# roomautomationfinal.net
KiCad netlist of a schematic drawn in EAGLE
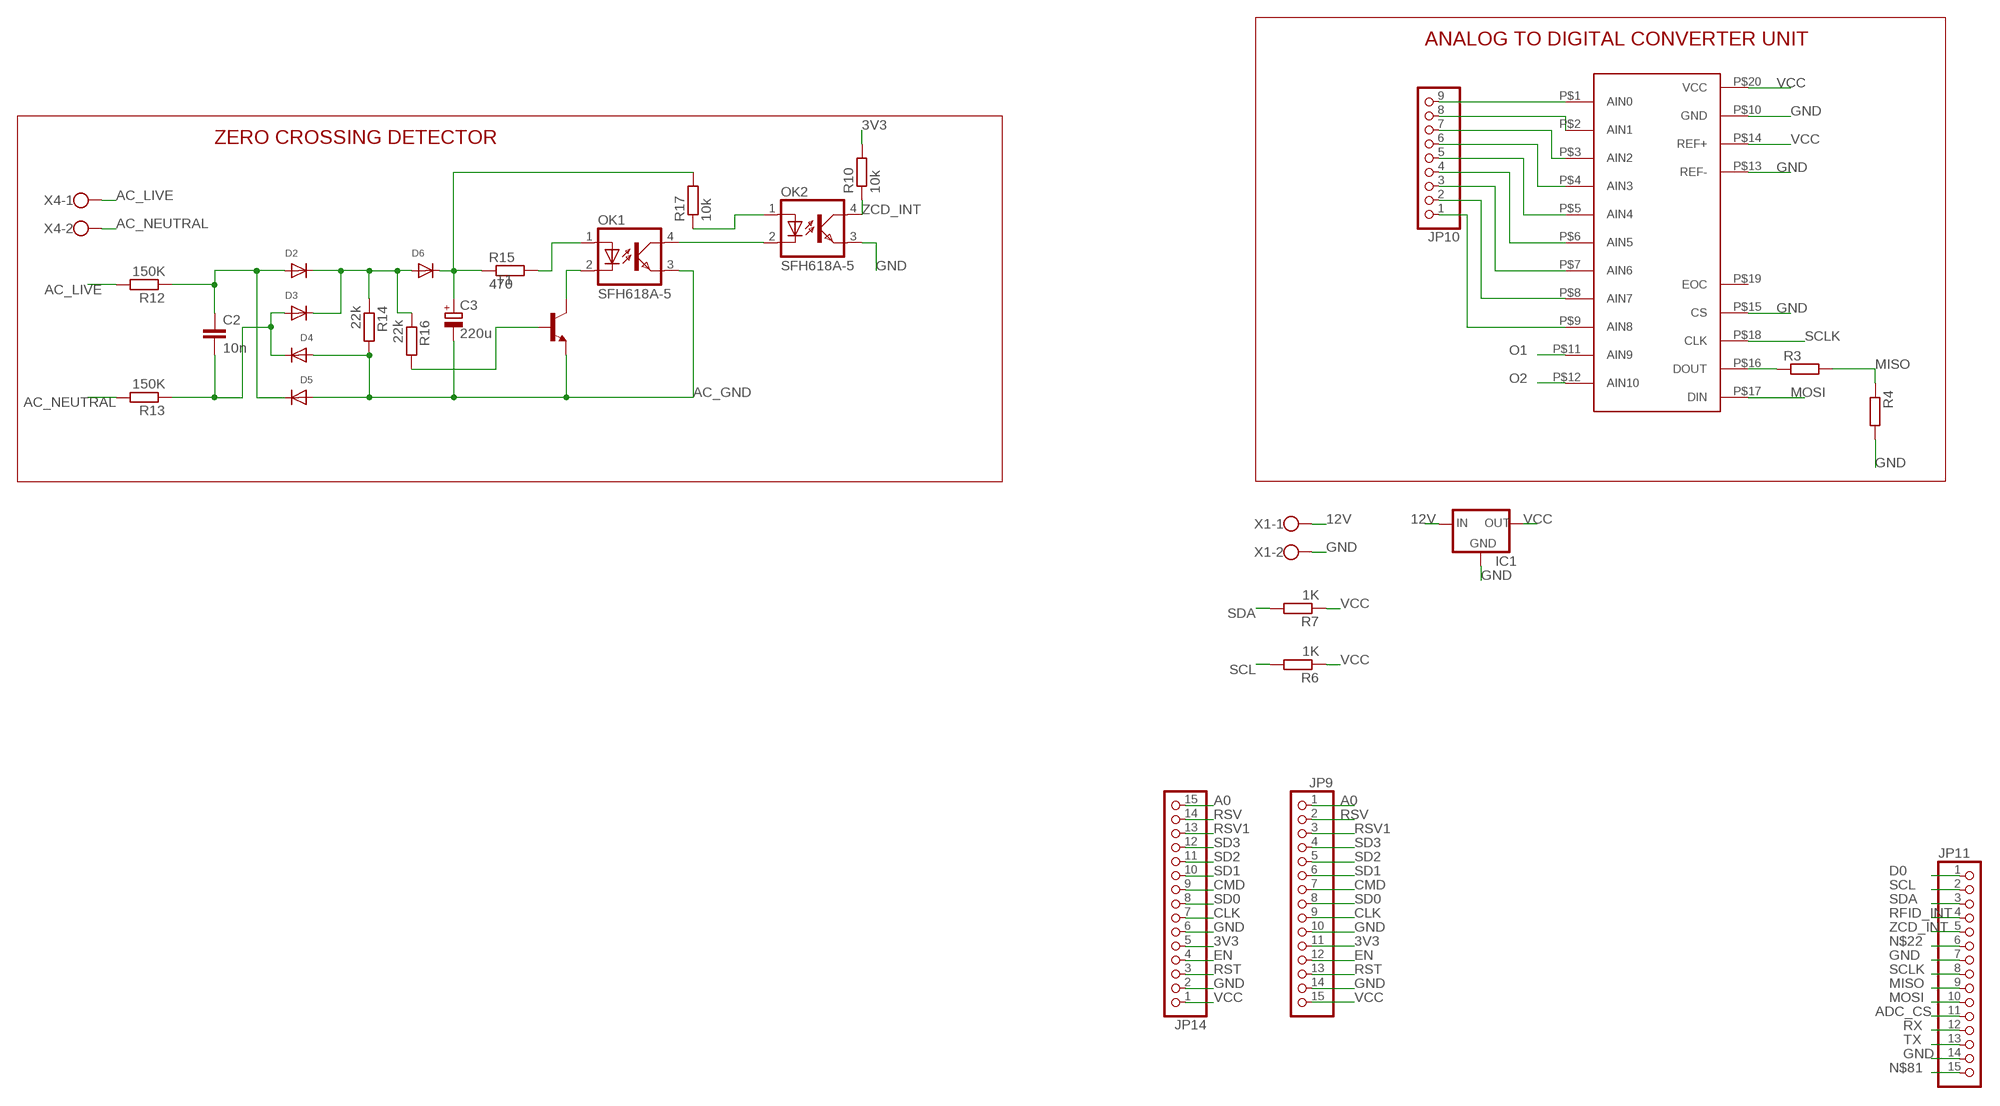
[diagram p0: schematic, sheet 1, part 1 of 2]
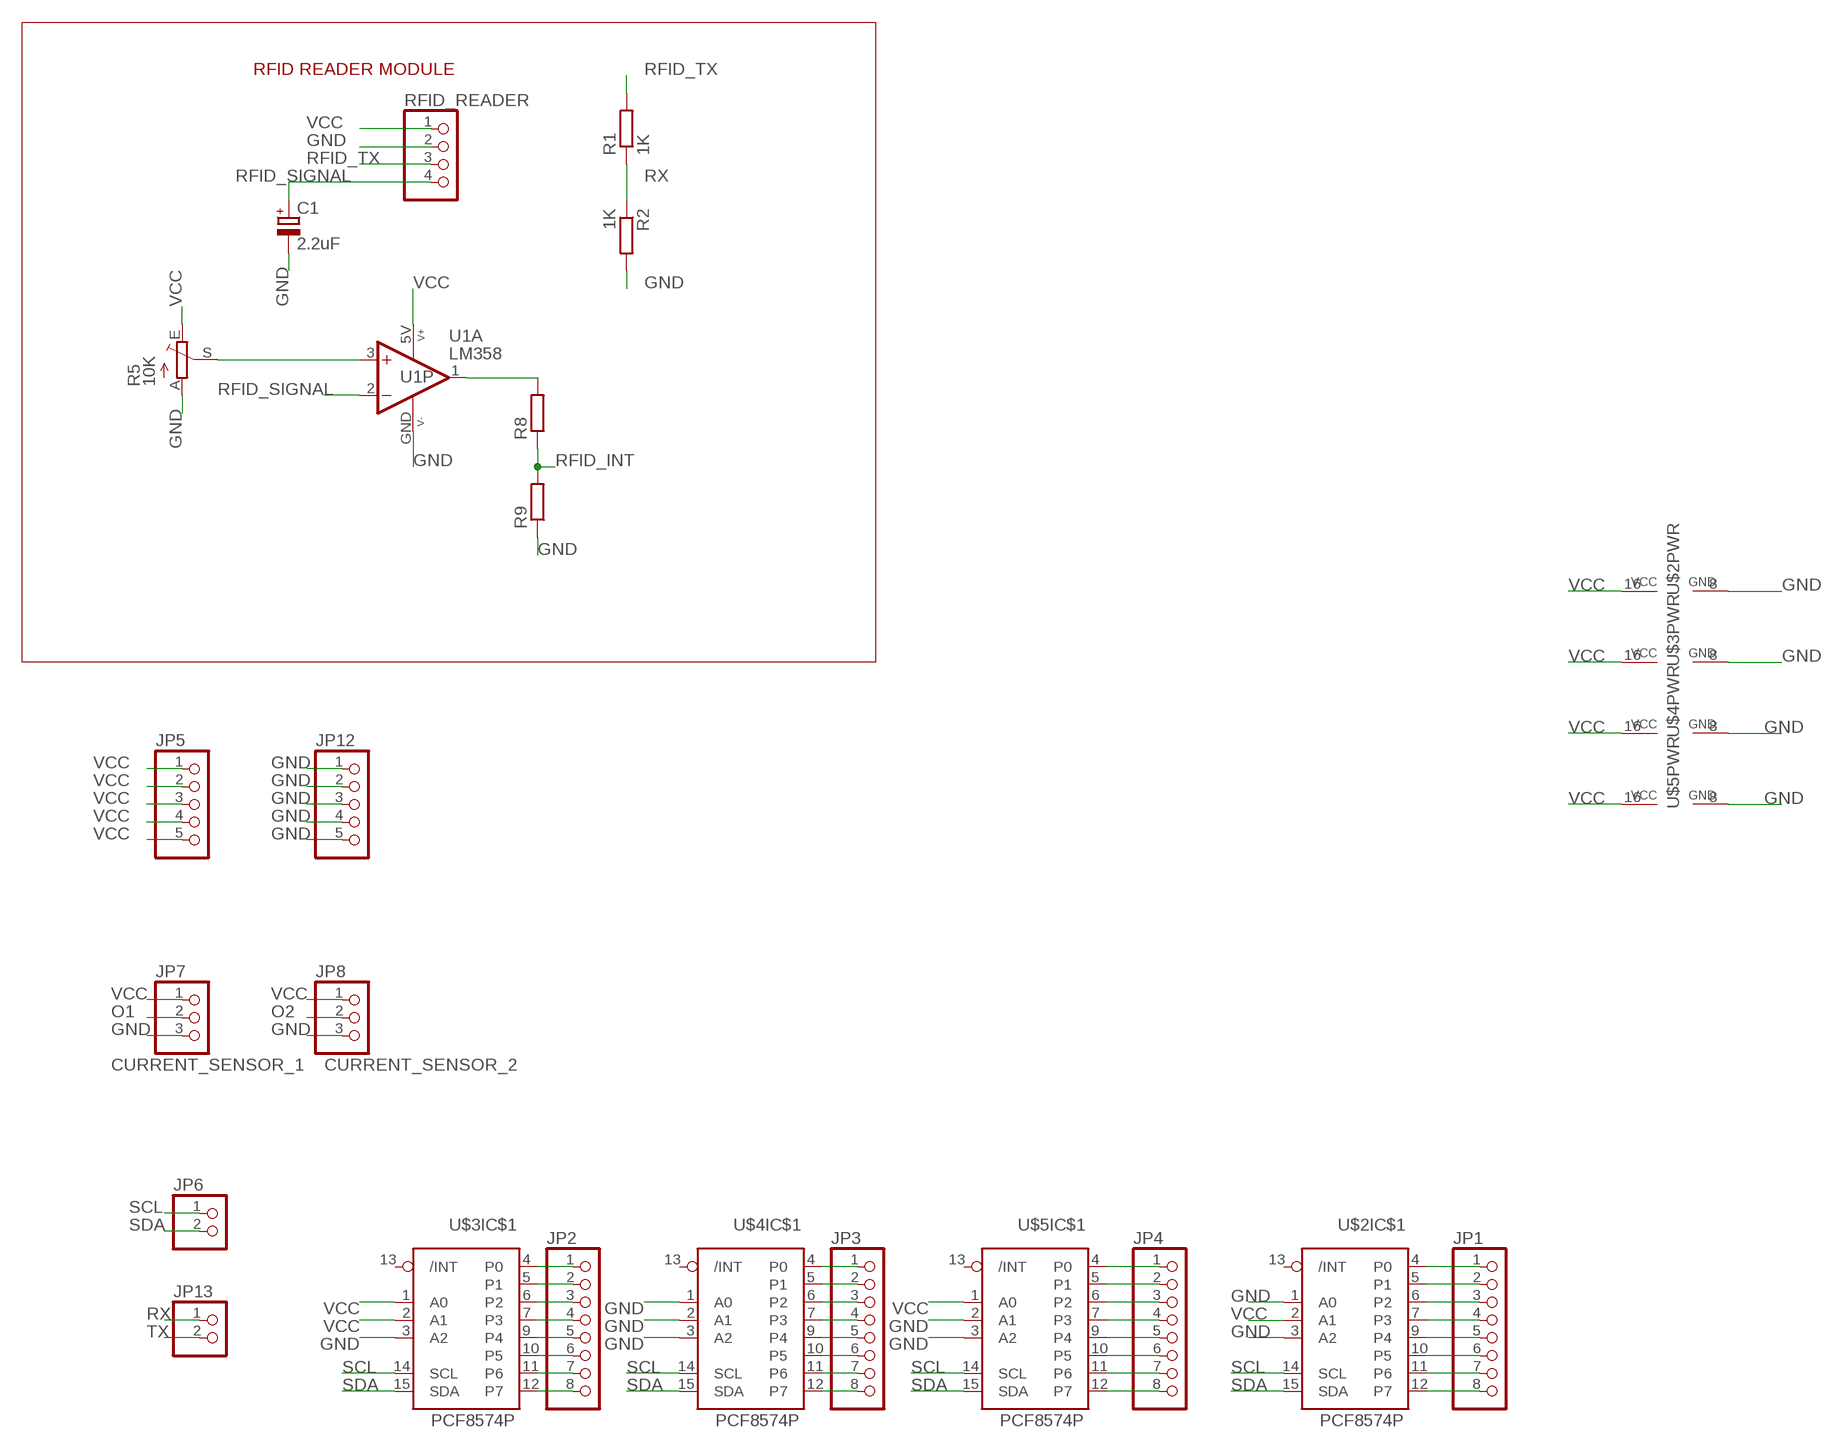
[diagram p1: schematic, sheet 1, part 2 of 2]

(export (version "E")
  (design (tool "Eeschema 10.0.6"))
  (components
    (comp (ref "C1")
      (value "2.2uF")
      (footprint "eagle-import:E2,5-5")
      (libsource (lib "eagle-import") (part "resistor_CPOL-EUE2.5-5"))
    )
    (comp (ref "C2")
      (value "10n")
      (footprint "eagle-import:C150-054X183")
      (libsource (lib "eagle-import") (part "C-EU150-054X183"))
    )
    (comp (ref "C3")
      (value "220u")
      (footprint "eagle-import:E5-10,5")
      (libsource (lib "eagle-import") (part "CPOL-EUE5-10.5"))
    )
    (comp (ref "D2")
      (value "DIODEDO-1N4148")
      (footprint "eagle-import:DO-1N4148")
      (libsource (lib "eagle-import") (part "DIODEDO-1N4148"))
    )
    (comp (ref "D3")
      (value "DIODEDO-1N4148")
      (footprint "eagle-import:DO-1N4148")
      (libsource (lib "eagle-import") (part "DIODEDO-1N4148"))
    )
    (comp (ref "D4")
      (value "DIODEDO-1N4148")
      (footprint "eagle-import:DO-1N4148")
      (libsource (lib "eagle-import") (part "DIODEDO-1N4148"))
    )
    (comp (ref "D5")
      (value "DIODEDO-1N4148")
      (footprint "eagle-import:DO-1N4148")
      (libsource (lib "eagle-import") (part "DIODEDO-1N4148"))
    )
    (comp (ref "D6")
      (value "DIODEDO-1N4148")
      (footprint "eagle-import:DO-1N4148")
      (libsource (lib "eagle-import") (part "DIODEDO-1N4148"))
    )
    (comp (ref "IC1")
      (value "78MXXS")
      (footprint "eagle-import:78MXXS")
      (libsource (lib "eagle-import") (part "78MXXS"))
    )
    (comp (ref "JP1")
      (value "HEADER-1X8")
      (footprint "eagle-import:1X08_OVAL")
      (libsource (lib "eagle-import") (part "HEADER-1X8"))
    )
    (comp (ref "JP2")
      (value "HEADER-1X8")
      (footprint "eagle-import:1X08_OVAL")
      (libsource (lib "eagle-import") (part "HEADER-1X8"))
    )
    (comp (ref "JP3")
      (value "HEADER-1X8")
      (footprint "eagle-import:1X08_OVAL")
      (libsource (lib "eagle-import") (part "HEADER-1X8"))
    )
    (comp (ref "JP4")
      (value "HEADER-1X8")
      (footprint "eagle-import:1X08_OVAL")
      (libsource (lib "eagle-import") (part "HEADER-1X8"))
    )
    (comp (ref "JP5")
      (value "PINHD-1X5")
      (footprint "eagle-import:1X05")
      (libsource (lib "eagle-import") (part "PINHD-1X5"))
    )
    (comp (ref "JP6")
      (value "PINHD-1X2")
      (footprint "eagle-import:1X02")
      (libsource (lib "eagle-import") (part "PINHD-1X2"))
    )
    (comp (ref "JP7")
      (value "PINHD-1X3")
      (footprint "eagle-import:1X03")
      (libsource (lib "eagle-import") (part "PINHD-1X3"))
    )
    (comp (ref "JP8")
      (value "PINHD-1X3")
      (footprint "eagle-import:1X03")
      (libsource (lib "eagle-import") (part "PINHD-1X3"))
    )
    (comp (ref "JP9")
      (value "PINHD-1X15")
      (footprint "eagle-import:1X15")
      (libsource (lib "eagle-import") (part "PINHD-1X15"))
    )
    (comp (ref "JP10")
      (value "PINHD-1X9")
      (footprint "eagle-import:1X09")
      (libsource (lib "eagle-import") (part "PINHD-1X9"))
    )
    (comp (ref "JP11")
      (value "PINHD-1X15")
      (footprint "eagle-import:1X15")
      (libsource (lib "eagle-import") (part "pinhead_PINHD-1X15"))
    )
    (comp (ref "JP12")
      (value "PINHD-1X5")
      (footprint "eagle-import:1X05")
      (libsource (lib "eagle-import") (part "PINHD-1X5"))
    )
    (comp (ref "JP13")
      (value "PINHD-1X2")
      (footprint "eagle-import:1X02")
      (libsource (lib "eagle-import") (part "PINHD-1X2"))
    )
    (comp (ref "JP14")
      (value "PINHD-1X15")
      (footprint "eagle-import:1X15")
      (libsource (lib "eagle-import") (part "pinhead_PINHD-1X15"))
    )
    (comp (ref "OK1")
      (value "SFH618A-5")
      (footprint "eagle-import:DIP4")
      (fields (field (name "MF") "VISHAY/TELEFUNKEN"))
      (libsource (lib "eagle-import") (part "SFH618?A-5"))
    )
    (comp (ref "OK2")
      (value "SFH618A-5")
      (footprint "eagle-import:DIP4")
      (fields
        (field (name "MF") "VISHAY/TELEFUNKEN")
        (field (name "MF_1") "VISHAY/TELEFUNKEN")
        (field (name "MPN") "SFH618A-5")
        (field (name "OC_FARNELL") "1469593")
        (field (name "OC_NEWARK") "59K0259")
      )
      (libsource (lib "eagle-import") (part "SFH618?A-5"))
    )
    (comp (ref "R1")
      (value "1K")
      (footprint "eagle-import:0207_10")
      (libsource (lib "eagle-import") (part "R-EU_0207/10"))
    )
    (comp (ref "R2")
      (value "1K")
      (footprint "eagle-import:0207_10")
      (libsource (lib "eagle-import") (part "R-EU_0207/10"))
    )
    (comp (ref "R3")
      (value "R-EU_0207/10")
      (footprint "eagle-import:0207_10")
      (libsource (lib "eagle-import") (part "R-EU_0207/10"))
    )
    (comp (ref "R4")
      (value "R-EU_0207/10")
      (footprint "eagle-import:0207_10")
      (libsource (lib "eagle-import") (part "R-EU_0207/10"))
    )
    (comp (ref "R5")
      (value "10K")
      (footprint "eagle-import:B25P")
      (libsource (lib "eagle-import") (part "TRIM_EU-B25P"))
    )
    (comp (ref "R6")
      (value "1K")
      (footprint "eagle-import:0207_10")
      (libsource (lib "eagle-import") (part "R-EU_0207/10"))
    )
    (comp (ref "R7")
      (value "1K")
      (footprint "eagle-import:0207_10")
      (libsource (lib "eagle-import") (part "R-EU_0207/10"))
    )
    (comp (ref "R8")
      (value "R-EU_0207/10")
      (footprint "eagle-import:0207_10")
      (libsource (lib "eagle-import") (part "R-EU_0207/10"))
    )
    (comp (ref "R9")
      (value "R-EU_0207/10")
      (footprint "eagle-import:0207_10")
      (libsource (lib "eagle-import") (part "R-EU_0207/10"))
    )
    (comp (ref "R10")
      (value "10k")
      (footprint "eagle-import:0207_10")
      (libsource (lib "eagle-import") (part "R-EU_0207/10"))
    )
    (comp (ref "R12")
      (value "150K")
      (footprint "eagle-import:0207_10")
      (libsource (lib "eagle-import") (part "R-EU_0207/10"))
    )
    (comp (ref "R13")
      (value "150K")
      (footprint "eagle-import:0207_10")
      (libsource (lib "eagle-import") (part "R-EU_0207/10"))
    )
    (comp (ref "R14")
      (value "22k")
      (footprint "eagle-import:0207_10")
      (libsource (lib "eagle-import") (part "R-EU_0207/10"))
    )
    (comp (ref "R15")
      (value "470")
      (footprint "eagle-import:0617V")
      (libsource (lib "eagle-import") (part "R-EU_0617/5V"))
    )
    (comp (ref "R16")
      (value "22k")
      (footprint "eagle-import:0207_10")
      (libsource (lib "eagle-import") (part "R-EU_0207/10"))
    )
    (comp (ref "R17")
      (value "10k")
      (footprint "eagle-import:0617V")
      (libsource (lib "eagle-import") (part "R-EU_0617/5V"))
    )
    (comp (ref "RFID_READER")
      (value "HEADER-1X4")
      (footprint "eagle-import:1X04_OVAL")
      (libsource (lib "eagle-import") (part "HEADER-1X4"))
    )
    (comp (ref "T1")
      (value "-NPN-TO92-CBE")
      (footprint "eagle-import:TO92-CBE")
      (libsource (lib "eagle-import") (part "-NPN-TO92-CBE"))
    )
    (comp (ref "U$2")
      (value "PCF8574P")
      (footprint "eagle-import:DIL16")
      (libsource (lib "eagle-import") (part "PCF8574P"))
    )
    (comp (ref "U$3")
      (value "PCF8574P")
      (footprint "eagle-import:DIL16")
      (libsource (lib "eagle-import") (part "PCF8574P"))
    )
    (comp (ref "U$4")
      (value "PCF8574P")
      (footprint "eagle-import:DIL16")
      (libsource (lib "eagle-import") (part "PCF8574P"))
    )
    (comp (ref "U$5")
      (value "PCF8574P")
      (footprint "eagle-import:DIL16")
      (libsource (lib "eagle-import") (part "PCF8574P"))
    )
    (comp (ref "U$6")
      (value "TLC2543")
      (footprint "eagle-import:TLC2543")
      (libsource (lib "eagle-import") (part "TLC2543"))
    )
    (comp (ref "U1")
      (value "LM358")
      (footprint "eagle-import:DIL08")
      (libsource (lib "eagle-import") (part "NE5532N"))
    )
    (comp (ref "X1")
      (value "W237-102")
      (footprint "eagle-import:W237-102")
      (fields (field (name "MPN") "237-102"))
      (libsource (lib "eagle-import") (part "W237-102"))
    )
    (comp (ref "X4")
      (value "W237-102")
      (footprint "eagle-import:W237-102")
      (fields
        (field (name "MPN") "237-102")
        (field (name "MPN_1") "237-102")
        (field (name "OC_FARNELL") "unknown")
        (field (name "OC_NEWARK") "70K9898")
      )
      (libsource (lib "eagle-import") (part "W237-102"))
    )
  )
  (nets
    (net (code "1") (name "/3V3") (class "Default")
      (node (ref "JP14") (pin "5") (pinfunction "5_5") (pintype "passive"))
      (node (ref "JP9") (pin "11") (pinfunction "11_11") (pintype "passive"))
      (node (ref "R10") (pin "2") (pinfunction "2_2") (pintype "passive"))
    )
    (net (code "2") (name "/12V") (class "Default")
      (node (ref "IC1") (pin "IN") (pinfunction "IN_IN") (pintype "input"))
      (node (ref "X1") (pin "1") (pinfunction "KL_1") (pintype "passive"))
    )
    (net (code "3") (name "/A0") (class "Default")
      (node (ref "JP14") (pin "15") (pinfunction "15_15") (pintype "passive"))
      (node (ref "JP9") (pin "1") (pinfunction "1_1") (pintype "passive"))
    )
    (net (code "4") (name "/AC_GND") (class "Default")
      (node (ref "C3") (pin "-") (pinfunction "-_-") (pintype "passive"))
      (node (ref "D4") (pin "A") (pinfunction "A_A") (pintype "passive"))
      (node (ref "D5") (pin "A") (pinfunction "A_A") (pintype "passive"))
      (node (ref "OK1") (pin "3") (pinfunction "EMIT_3") (pintype "passive"))
      (node (ref "R14") (pin "2") (pinfunction "2_2") (pintype "passive"))
      (node (ref "T1") (pin "E") (pinfunction "E_E") (pintype "passive"))
    )
    (net (code "5") (name "/AC_LIVE") (class "Default")
      (node (ref "R12") (pin "2") (pinfunction "2_2") (pintype "passive"))
      (node (ref "X4") (pin "1") (pinfunction "KL_1") (pintype "passive"))
    )
    (net (code "6") (name "/AC_NEUTRAL") (class "Default")
      (node (ref "R13") (pin "2") (pinfunction "2_2") (pintype "passive"))
      (node (ref "X4") (pin "2") (pinfunction "KL_2") (pintype "passive"))
    )
    (net (code "7") (name "/ADC_CS") (class "Default")
      (node (ref "JP11") (pin "11") (pinfunction "11_11") (pintype "passive"))
    )
    (net (code "8") (name "/CLK") (class "Default")
      (node (ref "JP14") (pin "7") (pinfunction "7_7") (pintype "passive"))
      (node (ref "JP9") (pin "9") (pinfunction "9_9") (pintype "passive"))
    )
    (net (code "9") (name "/CMD") (class "Default")
      (node (ref "JP14") (pin "9") (pinfunction "9_9") (pintype "passive"))
      (node (ref "JP9") (pin "7") (pinfunction "7_7") (pintype "passive"))
    )
    (net (code "10") (name "/D0") (class "Default")
      (node (ref "JP11") (pin "1") (pinfunction "1_1") (pintype "passive"))
    )
    (net (code "11") (name "/EN") (class "Default")
      (node (ref "JP14") (pin "4") (pinfunction "4_4") (pintype "passive"))
      (node (ref "JP9") (pin "12") (pinfunction "12_12") (pintype "passive"))
    )
    (net (code "12") (name "/GND") (class "Default")
      (node (ref "C1") (pin "-") (pinfunction "-_-") (pintype "passive"))
      (node (ref "IC1") (pin "GND") (pinfunction "GND_GND") (pintype "input"))
      (node (ref "JP11") (pin "14") (pinfunction "14_14") (pintype "passive"))
      (node (ref "JP11") (pin "7") (pinfunction "7_7") (pintype "passive"))
      (node (ref "JP12") (pin "1") (pinfunction "1_1") (pintype "passive"))
      (node (ref "JP12") (pin "2") (pinfunction "2_2") (pintype "passive"))
      (node (ref "JP12") (pin "3") (pinfunction "3_3") (pintype "passive"))
      (node (ref "JP12") (pin "4") (pinfunction "4_4") (pintype "passive"))
      (node (ref "JP12") (pin "5") (pinfunction "5_5") (pintype "passive"))
      (node (ref "JP14") (pin "2") (pinfunction "2_2") (pintype "passive"))
      (node (ref "JP14") (pin "6") (pinfunction "6_6") (pintype "passive"))
      (node (ref "JP7") (pin "3") (pinfunction "3_3") (pintype "passive"))
      (node (ref "JP8") (pin "3") (pinfunction "3_3") (pintype "passive"))
      (node (ref "JP9") (pin "10") (pinfunction "10_10") (pintype "passive"))
      (node (ref "JP9") (pin "14") (pinfunction "14_14") (pintype "passive"))
      (node (ref "OK2") (pin "3") (pinfunction "EMIT_3") (pintype "passive"))
      (node (ref "R2") (pin "2") (pinfunction "2_2") (pintype "passive"))
      (node (ref "R4") (pin "2") (pinfunction "2_2") (pintype "passive"))
      (node (ref "R5") (pin "A") (pinfunction "A_A") (pintype "passive"))
      (node (ref "R9") (pin "1") (pinfunction "1_1") (pintype "passive"))
      (node (ref "RFID_READER") (pin "2") (pinfunction "2_2") (pintype "passive"))
      (node (ref "U$2") (pin "1") (pinfunction "A0_1") (pintype "input"))
      (node (ref "U$2") (pin "3") (pinfunction "A2_3") (pintype "input"))
      (node (ref "U$2") (pin "8") (pinfunction "GND_8") (pintype "power_in"))
      (node (ref "U$3") (pin "3") (pinfunction "A2_3") (pintype "input"))
      (node (ref "U$3") (pin "8") (pinfunction "GND_8") (pintype "power_in"))
      (node (ref "U$4") (pin "1") (pinfunction "A0_1") (pintype "input"))
      (node (ref "U$4") (pin "2") (pinfunction "A1_2") (pintype "input"))
      (node (ref "U$4") (pin "3") (pinfunction "A2_3") (pintype "input"))
      (node (ref "U$4") (pin "8") (pinfunction "GND_8") (pintype "power_in"))
      (node (ref "U$5") (pin "2") (pinfunction "A1_2") (pintype "input"))
      (node (ref "U$5") (pin "3") (pinfunction "A2_3") (pintype "input"))
      (node (ref "U$5") (pin "8") (pinfunction "GND_8") (pintype "power_in"))
      (node (ref "U$6") (pin "P$10") (pinfunction "GND_P$10") (pintype "bidirectional"))
      (node (ref "U$6") (pin "P$13") (pinfunction "REF-_P$13") (pintype "bidirectional"))
      (node (ref "U$6") (pin "P$15") (pinfunction "CS_P$15") (pintype "bidirectional"))
      (node (ref "U1") (pin "GND") (pinfunction "V-_GND") (pintype "power_in"))
      (node (ref "X1") (pin "2") (pinfunction "KL_2") (pintype "passive"))
    )
    (net (code "13") (name "/MISO") (class "Default")
      (node (ref "JP11") (pin "9") (pinfunction "9_9") (pintype "passive"))
      (node (ref "R3") (pin "2") (pinfunction "2_2") (pintype "passive"))
      (node (ref "R4") (pin "1") (pinfunction "1_1") (pintype "passive"))
    )
    (net (code "14") (name "/MOSI") (class "Default")
      (node (ref "JP11") (pin "10") (pinfunction "10_10") (pintype "passive"))
      (node (ref "U$6") (pin "P$17") (pinfunction "DIN_P$17") (pintype "bidirectional"))
    )
    (net (code "15") (name "/N$22") (class "Default")
      (node (ref "JP11") (pin "6") (pinfunction "6_6") (pintype "passive"))
    )
    (net (code "16") (name "/N$81") (class "Default")
      (node (ref "JP11") (pin "15") (pinfunction "15_15") (pintype "passive"))
    )
    (net (code "17") (name "/O1") (class "Default")
      (node (ref "JP7") (pin "2") (pinfunction "2_2") (pintype "passive"))
      (node (ref "U$6") (pin "P$11") (pinfunction "AIN9_P$11") (pintype "bidirectional"))
    )
    (net (code "18") (name "/O2") (class "Default")
      (node (ref "JP8") (pin "2") (pinfunction "2_2") (pintype "passive"))
      (node (ref "U$6") (pin "P$12") (pinfunction "AIN10_P$12") (pintype "bidirectional"))
    )
    (net (code "19") (name "/RFID_INT") (class "Default")
      (node (ref "JP11") (pin "4") (pinfunction "4_4") (pintype "passive"))
      (node (ref "R8") (pin "1") (pinfunction "1_1") (pintype "passive"))
      (node (ref "R9") (pin "2") (pinfunction "2_2") (pintype "passive"))
    )
    (net (code "20") (name "/RFID_SIGNAL") (class "Default")
      (node (ref "C1") (pin "+") (pinfunction "+_+") (pintype "passive"))
      (node (ref "RFID_READER") (pin "4") (pinfunction "4_4") (pintype "passive"))
      (node (ref "U1") (pin "2") (pinfunction "-IN_2") (pintype "input"))
    )
    (net (code "21") (name "/RFID_TX") (class "Default")
      (node (ref "R1") (pin "2") (pinfunction "2_2") (pintype "passive"))
      (node (ref "RFID_READER") (pin "3") (pinfunction "3_3") (pintype "passive"))
    )
    (net (code "22") (name "/RST") (class "Default")
      (node (ref "JP14") (pin "3") (pinfunction "3_3") (pintype "passive"))
      (node (ref "JP9") (pin "13") (pinfunction "13_13") (pintype "passive"))
    )
    (net (code "23") (name "/RSV") (class "Default")
      (node (ref "JP14") (pin "14") (pinfunction "14_14") (pintype "passive"))
      (node (ref "JP9") (pin "2") (pinfunction "2_2") (pintype "passive"))
    )
    (net (code "24") (name "/RSV1") (class "Default")
      (node (ref "JP14") (pin "13") (pinfunction "13_13") (pintype "passive"))
      (node (ref "JP9") (pin "3") (pinfunction "3_3") (pintype "passive"))
    )
    (net (code "25") (name "/RX") (class "Default")
      (node (ref "JP11") (pin "12") (pinfunction "12_12") (pintype "passive"))
      (node (ref "JP13") (pin "1") (pinfunction "1_1") (pintype "passive"))
      (node (ref "R1") (pin "1") (pinfunction "1_1") (pintype "passive"))
      (node (ref "R2") (pin "1") (pinfunction "1_1") (pintype "passive"))
    )
    (net (code "26") (name "/SCL") (class "Default")
      (node (ref "JP11") (pin "2") (pinfunction "2_2") (pintype "passive"))
      (node (ref "JP6") (pin "1") (pinfunction "1_1") (pintype "passive"))
      (node (ref "R6") (pin "2") (pinfunction "2_2") (pintype "passive"))
      (node (ref "U$2") (pin "14") (pinfunction "SCL_14") (pintype "input"))
      (node (ref "U$3") (pin "14") (pinfunction "SCL_14") (pintype "input"))
      (node (ref "U$4") (pin "14") (pinfunction "SCL_14") (pintype "input"))
      (node (ref "U$5") (pin "14") (pinfunction "SCL_14") (pintype "input"))
    )
    (net (code "27") (name "/SCLK") (class "Default")
      (node (ref "JP11") (pin "8") (pinfunction "8_8") (pintype "passive"))
      (node (ref "U$6") (pin "P$18") (pinfunction "CLK_P$18") (pintype "bidirectional"))
    )
    (net (code "28") (name "/SD0") (class "Default")
      (node (ref "JP14") (pin "8") (pinfunction "8_8") (pintype "passive"))
      (node (ref "JP9") (pin "8") (pinfunction "8_8") (pintype "passive"))
    )
    (net (code "29") (name "/SD1") (class "Default")
      (node (ref "JP14") (pin "10") (pinfunction "10_10") (pintype "passive"))
      (node (ref "JP9") (pin "6") (pinfunction "6_6") (pintype "passive"))
    )
    (net (code "30") (name "/SD2") (class "Default")
      (node (ref "JP14") (pin "11") (pinfunction "11_11") (pintype "passive"))
      (node (ref "JP9") (pin "5") (pinfunction "5_5") (pintype "passive"))
    )
    (net (code "31") (name "/SD3") (class "Default")
      (node (ref "JP14") (pin "12") (pinfunction "12_12") (pintype "passive"))
      (node (ref "JP9") (pin "4") (pinfunction "4_4") (pintype "passive"))
    )
    (net (code "32") (name "/SDA") (class "Default")
      (node (ref "JP11") (pin "3") (pinfunction "3_3") (pintype "passive"))
      (node (ref "JP6") (pin "2") (pinfunction "2_2") (pintype "passive"))
      (node (ref "R7") (pin "2") (pinfunction "2_2") (pintype "passive"))
      (node (ref "U$2") (pin "15") (pinfunction "SDA_15") (pintype "bidirectional"))
      (node (ref "U$3") (pin "15") (pinfunction "SDA_15") (pintype "bidirectional"))
      (node (ref "U$4") (pin "15") (pinfunction "SDA_15") (pintype "bidirectional"))
      (node (ref "U$5") (pin "15") (pinfunction "SDA_15") (pintype "bidirectional"))
    )
    (net (code "33") (name "/TX") (class "Default")
      (node (ref "JP11") (pin "13") (pinfunction "13_13") (pintype "passive"))
      (node (ref "JP13") (pin "2") (pinfunction "2_2") (pintype "passive"))
    )
    (net (code "34") (name "/VCC") (class "Default")
      (node (ref "IC1") (pin "OUT") (pinfunction "OUT_OUT") (pintype "passive"))
      (node (ref "JP14") (pin "1") (pinfunction "1_1") (pintype "passive"))
      (node (ref "JP5") (pin "1") (pinfunction "1_1") (pintype "passive"))
      (node (ref "JP5") (pin "2") (pinfunction "2_2") (pintype "passive"))
      (node (ref "JP5") (pin "3") (pinfunction "3_3") (pintype "passive"))
      (node (ref "JP5") (pin "4") (pinfunction "4_4") (pintype "passive"))
      (node (ref "JP5") (pin "5") (pinfunction "5_5") (pintype "passive"))
      (node (ref "JP7") (pin "1") (pinfunction "1_1") (pintype "passive"))
      (node (ref "JP8") (pin "1") (pinfunction "1_1") (pintype "passive"))
      (node (ref "JP9") (pin "15") (pinfunction "15_15") (pintype "passive"))
      (node (ref "R5") (pin "E") (pinfunction "E_E") (pintype "passive"))
      (node (ref "R6") (pin "1") (pinfunction "1_1") (pintype "passive"))
      (node (ref "R7") (pin "1") (pinfunction "1_1") (pintype "passive"))
      (node (ref "RFID_READER") (pin "1") (pinfunction "1_1") (pintype "passive"))
      (node (ref "U$2") (pin "16") (pinfunction "VCC_16") (pintype "power_in"))
      (node (ref "U$2") (pin "2") (pinfunction "A1_2") (pintype "input"))
      (node (ref "U$3") (pin "1") (pinfunction "A0_1") (pintype "input"))
      (node (ref "U$3") (pin "16") (pinfunction "VCC_16") (pintype "power_in"))
      (node (ref "U$3") (pin "2") (pinfunction "A1_2") (pintype "input"))
      (node (ref "U$4") (pin "16") (pinfunction "VCC_16") (pintype "power_in"))
      (node (ref "U$5") (pin "1") (pinfunction "A0_1") (pintype "input"))
      (node (ref "U$5") (pin "16") (pinfunction "VCC_16") (pintype "power_in"))
      (node (ref "U$6") (pin "P$14") (pinfunction "REF+_P$14") (pintype "bidirectional"))
      (node (ref "U$6") (pin "P$20") (pinfunction "VCC_P$20") (pintype "bidirectional"))
      (node (ref "U1") (pin "5V") (pinfunction "V+_5V") (pintype "power_in"))
    )
    (net (code "35") (name "/ZCD_INT") (class "Default")
      (node (ref "JP11") (pin "5") (pinfunction "5_5") (pintype "passive"))
      (node (ref "OK2") (pin "4") (pinfunction "COL_4") (pintype "passive"))
      (node (ref "R10") (pin "1") (pinfunction "1_1") (pintype "passive"))
    )
    (net (code "36") (name "Net-(C2-Pad1)") (class "Default")
      (node (ref "C2") (pin "1") (pinfunction "1_1") (pintype "passive"))
      (node (ref "D2") (pin "A") (pinfunction "A_A") (pintype "passive"))
      (node (ref "D5") (pin "C") (pinfunction "C_C") (pintype "passive"))
      (node (ref "R12") (pin "1") (pinfunction "1_1") (pintype "passive"))
    )
    (net (code "37") (name "Net-(C2-Pad2)") (class "Default")
      (node (ref "C2") (pin "2") (pinfunction "2_2") (pintype "passive"))
      (node (ref "D3") (pin "A") (pinfunction "A_A") (pintype "passive"))
      (node (ref "D4") (pin "C") (pinfunction "C_C") (pintype "passive"))
      (node (ref "R13") (pin "1") (pinfunction "1_1") (pintype "passive"))
    )
    (net (code "38") (name "Net-(C3-Pad+)") (class "Default")
      (node (ref "C3") (pin "+") (pinfunction "+_+") (pintype "passive"))
      (node (ref "D6") (pin "C") (pinfunction "C_C") (pintype "passive"))
      (node (ref "R15") (pin "1") (pinfunction "1_1") (pintype "passive"))
      (node (ref "R17") (pin "2") (pinfunction "2_2") (pintype "passive"))
    )
    (net (code "39") (name "Net-(D2-PadC)") (class "Default")
      (node (ref "D2") (pin "C") (pinfunction "C_C") (pintype "passive"))
      (node (ref "D3") (pin "C") (pinfunction "C_C") (pintype "passive"))
      (node (ref "D6") (pin "A") (pinfunction "A_A") (pintype "passive"))
      (node (ref "R14") (pin "1") (pinfunction "1_1") (pintype "passive"))
      (node (ref "R16") (pin "1") (pinfunction "1_1") (pintype "passive"))
    )
    (net (code "40") (name "Net-(OK1-A)") (class "Default")
      (node (ref "OK1") (pin "1") (pinfunction "A_1") (pintype "passive"))
      (node (ref "R15") (pin "2") (pinfunction "2_2") (pintype "passive"))
    )
    (net (code "41") (name "Net-(OK1-C)") (class "Default")
      (node (ref "OK1") (pin "2") (pinfunction "C_2") (pintype "passive"))
      (node (ref "T1") (pin "C") (pinfunction "C_C") (pintype "passive"))
    )
    (net (code "42") (name "Net-(OK1-COL)") (class "Default")
      (node (ref "OK1") (pin "4") (pinfunction "COL_4") (pintype "passive"))
      (node (ref "OK2") (pin "2") (pinfunction "C_2") (pintype "passive"))
    )
    (net (code "43") (name "Net-(OK2-A)") (class "Default")
      (node (ref "OK2") (pin "1") (pinfunction "A_1") (pintype "passive"))
      (node (ref "R17") (pin "1") (pinfunction "1_1") (pintype "passive"))
    )
    (net (code "44") (name "Net-(R16-Pad2)") (class "Default")
      (node (ref "R16") (pin "2") (pinfunction "2_2") (pintype "passive"))
      (node (ref "T1") (pin "B") (pinfunction "B_B") (pintype "passive"))
    )
    (net (code "45") (name "Net-(U$2A-P0)") (class "Default")
      (node (ref "JP1") (pin "1") (pinfunction "1_1") (pintype "passive"))
      (node (ref "U$2") (pin "4") (pinfunction "P0_4") (pintype "bidirectional"))
    )
    (net (code "46") (name "Net-(U$2A-P1)") (class "Default")
      (node (ref "JP1") (pin "2") (pinfunction "2_2") (pintype "passive"))
      (node (ref "U$2") (pin "5") (pinfunction "P1_5") (pintype "bidirectional"))
    )
    (net (code "47") (name "Net-(U$2A-P2)") (class "Default")
      (node (ref "JP1") (pin "3") (pinfunction "3_3") (pintype "passive"))
      (node (ref "U$2") (pin "6") (pinfunction "P2_6") (pintype "bidirectional"))
    )
    (net (code "48") (name "Net-(U$2A-P3)") (class "Default")
      (node (ref "JP1") (pin "4") (pinfunction "4_4") (pintype "passive"))
      (node (ref "U$2") (pin "7") (pinfunction "P3_7") (pintype "bidirectional"))
    )
    (net (code "49") (name "Net-(U$2A-P4)") (class "Default")
      (node (ref "JP1") (pin "5") (pinfunction "5_5") (pintype "passive"))
      (node (ref "U$2") (pin "9") (pinfunction "P4_9") (pintype "bidirectional"))
    )
    (net (code "50") (name "Net-(U$2A-P5)") (class "Default")
      (node (ref "JP1") (pin "6") (pinfunction "6_6") (pintype "passive"))
      (node (ref "U$2") (pin "10") (pinfunction "P5_10") (pintype "bidirectional"))
    )
    (net (code "51") (name "Net-(U$2A-P6)") (class "Default")
      (node (ref "JP1") (pin "7") (pinfunction "7_7") (pintype "passive"))
      (node (ref "U$2") (pin "11") (pinfunction "P6_11") (pintype "bidirectional"))
    )
    (net (code "52") (name "Net-(U$2A-P7)") (class "Default")
      (node (ref "JP1") (pin "8") (pinfunction "8_8") (pintype "passive"))
      (node (ref "U$2") (pin "12") (pinfunction "P7_12") (pintype "bidirectional"))
    )
    (net (code "53") (name "Net-(U$3A-P0)") (class "Default")
      (node (ref "JP2") (pin "1") (pinfunction "1_1") (pintype "passive"))
      (node (ref "U$3") (pin "4") (pinfunction "P0_4") (pintype "bidirectional"))
    )
    (net (code "54") (name "Net-(U$3A-P1)") (class "Default")
      (node (ref "JP2") (pin "2") (pinfunction "2_2") (pintype "passive"))
      (node (ref "U$3") (pin "5") (pinfunction "P1_5") (pintype "bidirectional"))
    )
    (net (code "55") (name "Net-(U$3A-P2)") (class "Default")
      (node (ref "JP2") (pin "3") (pinfunction "3_3") (pintype "passive"))
      (node (ref "U$3") (pin "6") (pinfunction "P2_6") (pintype "bidirectional"))
    )
    (net (code "56") (name "Net-(U$3A-P3)") (class "Default")
      (node (ref "JP2") (pin "4") (pinfunction "4_4") (pintype "passive"))
      (node (ref "U$3") (pin "7") (pinfunction "P3_7") (pintype "bidirectional"))
    )
    (net (code "57") (name "Net-(U$3A-P4)") (class "Default")
      (node (ref "JP2") (pin "5") (pinfunction "5_5") (pintype "passive"))
      (node (ref "U$3") (pin "9") (pinfunction "P4_9") (pintype "bidirectional"))
    )
    (net (code "58") (name "Net-(U$3A-P5)") (class "Default")
      (node (ref "JP2") (pin "6") (pinfunction "6_6") (pintype "passive"))
      (node (ref "U$3") (pin "10") (pinfunction "P5_10") (pintype "bidirectional"))
    )
    (net (code "59") (name "Net-(U$3A-P6)") (class "Default")
      (node (ref "JP2") (pin "7") (pinfunction "7_7") (pintype "passive"))
      (node (ref "U$3") (pin "11") (pinfunction "P6_11") (pintype "bidirectional"))
    )
    (net (code "60") (name "Net-(U$3A-P7)") (class "Default")
      (node (ref "JP2") (pin "8") (pinfunction "8_8") (pintype "passive"))
      (node (ref "U$3") (pin "12") (pinfunction "P7_12") (pintype "bidirectional"))
    )
    (net (code "61") (name "Net-(U$4A-P0)") (class "Default")
      (node (ref "JP3") (pin "1") (pinfunction "1_1") (pintype "passive"))
      (node (ref "U$4") (pin "4") (pinfunction "P0_4") (pintype "bidirectional"))
    )
    (net (code "62") (name "Net-(U$4A-P1)") (class "Default")
      (node (ref "JP3") (pin "2") (pinfunction "2_2") (pintype "passive"))
      (node (ref "U$4") (pin "5") (pinfunction "P1_5") (pintype "bidirectional"))
    )
    (net (code "63") (name "Net-(U$4A-P2)") (class "Default")
      (node (ref "JP3") (pin "3") (pinfunction "3_3") (pintype "passive"))
      (node (ref "U$4") (pin "6") (pinfunction "P2_6") (pintype "bidirectional"))
    )
    (net (code "64") (name "Net-(U$4A-P3)") (class "Default")
      (node (ref "JP3") (pin "4") (pinfunction "4_4") (pintype "passive"))
      (node (ref "U$4") (pin "7") (pinfunction "P3_7") (pintype "bidirectional"))
    )
    (net (code "65") (name "Net-(U$4A-P4)") (class "Default")
      (node (ref "JP3") (pin "5") (pinfunction "5_5") (pintype "passive"))
      (node (ref "U$4") (pin "9") (pinfunction "P4_9") (pintype "bidirectional"))
    )
    (net (code "66") (name "Net-(U$4A-P5)") (class "Default")
      (node (ref "JP3") (pin "6") (pinfunction "6_6") (pintype "passive"))
      (node (ref "U$4") (pin "10") (pinfunction "P5_10") (pintype "bidirectional"))
    )
    (net (code "67") (name "Net-(U$4A-P6)") (class "Default")
      (node (ref "JP3") (pin "7") (pinfunction "7_7") (pintype "passive"))
      (node (ref "U$4") (pin "11") (pinfunction "P6_11") (pintype "bidirectional"))
    )
    (net (code "68") (name "Net-(U$4A-P7)") (class "Default")
      (node (ref "JP3") (pin "8") (pinfunction "8_8") (pintype "passive"))
      (node (ref "U$4") (pin "12") (pinfunction "P7_12") (pintype "bidirectional"))
    )
    (net (code "69") (name "Net-(U$5A-P0)") (class "Default")
      (node (ref "JP4") (pin "1") (pinfunction "1_1") (pintype "passive"))
      (node (ref "U$5") (pin "4") (pinfunction "P0_4") (pintype "bidirectional"))
    )
    (net (code "70") (name "Net-(U$5A-P1)") (class "Default")
      (node (ref "JP4") (pin "2") (pinfunction "2_2") (pintype "passive"))
      (node (ref "U$5") (pin "5") (pinfunction "P1_5") (pintype "bidirectional"))
    )
    (net (code "71") (name "Net-(U$5A-P2)") (class "Default")
      (node (ref "JP4") (pin "3") (pinfunction "3_3") (pintype "passive"))
      (node (ref "U$5") (pin "6") (pinfunction "P2_6") (pintype "bidirectional"))
    )
    (net (code "72") (name "Net-(U$5A-P3)") (class "Default")
      (node (ref "JP4") (pin "4") (pinfunction "4_4") (pintype "passive"))
      (node (ref "U$5") (pin "7") (pinfunction "P3_7") (pintype "bidirectional"))
    )
    (net (code "73") (name "Net-(U$5A-P4)") (class "Default")
      (node (ref "JP4") (pin "5") (pinfunction "5_5") (pintype "passive"))
      (node (ref "U$5") (pin "9") (pinfunction "P4_9") (pintype "bidirectional"))
    )
    (net (code "74") (name "Net-(U$5A-P5)") (class "Default")
      (node (ref "JP4") (pin "6") (pinfunction "6_6") (pintype "passive"))
      (node (ref "U$5") (pin "10") (pinfunction "P5_10") (pintype "bidirectional"))
    )
    (net (code "75") (name "Net-(U$5A-P6)") (class "Default")
      (node (ref "JP4") (pin "7") (pinfunction "7_7") (pintype "passive"))
      (node (ref "U$5") (pin "11") (pinfunction "P6_11") (pintype "bidirectional"))
    )
    (net (code "76") (name "Net-(U$5A-P7)") (class "Default")
      (node (ref "JP4") (pin "8") (pinfunction "8_8") (pintype "passive"))
      (node (ref "U$5") (pin "12") (pinfunction "P7_12") (pintype "bidirectional"))
    )
    (net (code "77") (name "Net-(U$6-AIN0)") (class "Default")
      (node (ref "JP10") (pin "9") (pinfunction "9_9") (pintype "passive"))
      (node (ref "U$6") (pin "P$1") (pinfunction "AIN0_P$1") (pintype "bidirectional"))
    )
    (net (code "78") (name "Net-(U$6-AIN1)") (class "Default")
      (node (ref "JP10") (pin "8") (pinfunction "8_8") (pintype "passive"))
      (node (ref "U$6") (pin "P$2") (pinfunction "AIN1_P$2") (pintype "bidirectional"))
    )
    (net (code "79") (name "Net-(U$6-AIN2)") (class "Default")
      (node (ref "JP10") (pin "7") (pinfunction "7_7") (pintype "passive"))
      (node (ref "U$6") (pin "P$3") (pinfunction "AIN2_P$3") (pintype "bidirectional"))
    )
    (net (code "80") (name "Net-(U$6-AIN3)") (class "Default")
      (node (ref "JP10") (pin "6") (pinfunction "6_6") (pintype "passive"))
      (node (ref "U$6") (pin "P$4") (pinfunction "AIN3_P$4") (pintype "bidirectional"))
    )
    (net (code "81") (name "Net-(U$6-AIN4)") (class "Default")
      (node (ref "JP10") (pin "5") (pinfunction "5_5") (pintype "passive"))
      (node (ref "U$6") (pin "P$5") (pinfunction "AIN4_P$5") (pintype "bidirectional"))
    )
    (net (code "82") (name "Net-(U$6-AIN5)") (class "Default")
      (node (ref "JP10") (pin "4") (pinfunction "4_4") (pintype "passive"))
      (node (ref "U$6") (pin "P$6") (pinfunction "AIN5_P$6") (pintype "bidirectional"))
    )
    (net (code "83") (name "Net-(U$6-AIN6)") (class "Default")
      (node (ref "JP10") (pin "3") (pinfunction "3_3") (pintype "passive"))
      (node (ref "U$6") (pin "P$7") (pinfunction "AIN6_P$7") (pintype "bidirectional"))
    )
    (net (code "84") (name "Net-(U$6-AIN7)") (class "Default")
      (node (ref "JP10") (pin "2") (pinfunction "2_2") (pintype "passive"))
      (node (ref "U$6") (pin "P$8") (pinfunction "AIN7_P$8") (pintype "bidirectional"))
    )
    (net (code "85") (name "Net-(U$6-AIN8)") (class "Default")
      (node (ref "JP10") (pin "1") (pinfunction "1_1") (pintype "passive"))
      (node (ref "U$6") (pin "P$9") (pinfunction "AIN8_P$9") (pintype "bidirectional"))
    )
    (net (code "86") (name "Net-(U$6-DOUT)") (class "Default")
      (node (ref "R3") (pin "1") (pinfunction "1_1") (pintype "passive"))
      (node (ref "U$6") (pin "P$16") (pinfunction "DOUT_P$16") (pintype "bidirectional"))
    )
    (net (code "87") (name "Net-(U1A-+IN)") (class "Default")
      (node (ref "R5") (pin "S") (pinfunction "S_S") (pintype "passive"))
      (node (ref "U1") (pin "3") (pinfunction "+IN_3") (pintype "input"))
    )
    (net (code "88") (name "Net-(U1A-OUT)") (class "Default")
      (node (ref "R8") (pin "2") (pinfunction "2_2") (pintype "passive"))
      (node (ref "U1") (pin "1") (pinfunction "OUT_1") (pintype "output"))
    )
    (net (code "89") (name "unconnected-(U$2A-{slash}INT-Pad13)") (class "Default")
      (node (ref "U$2") (pin "13") (pinfunction "/INT_13") (pintype "output"))
    )
    (net (code "90") (name "unconnected-(U$3A-{slash}INT-Pad13)") (class "Default")
      (node (ref "U$3") (pin "13") (pinfunction "/INT_13") (pintype "output"))
    )
    (net (code "91") (name "unconnected-(U$4A-{slash}INT-Pad13)") (class "Default")
      (node (ref "U$4") (pin "13") (pinfunction "/INT_13") (pintype "output"))
    )
    (net (code "92") (name "unconnected-(U$5A-{slash}INT-Pad13)") (class "Default")
      (node (ref "U$5") (pin "13") (pinfunction "/INT_13") (pintype "output"))
    )
    (net (code "93") (name "unconnected-(U$6-EOC-PadP$19)") (class "Default")
      (node (ref "U$6") (pin "P$19") (pinfunction "EOC_P$19") (pintype "bidirectional"))
    )
  )
)
